# ProjV1.net
KiCad netlist of a schematic drawn in EAGLE
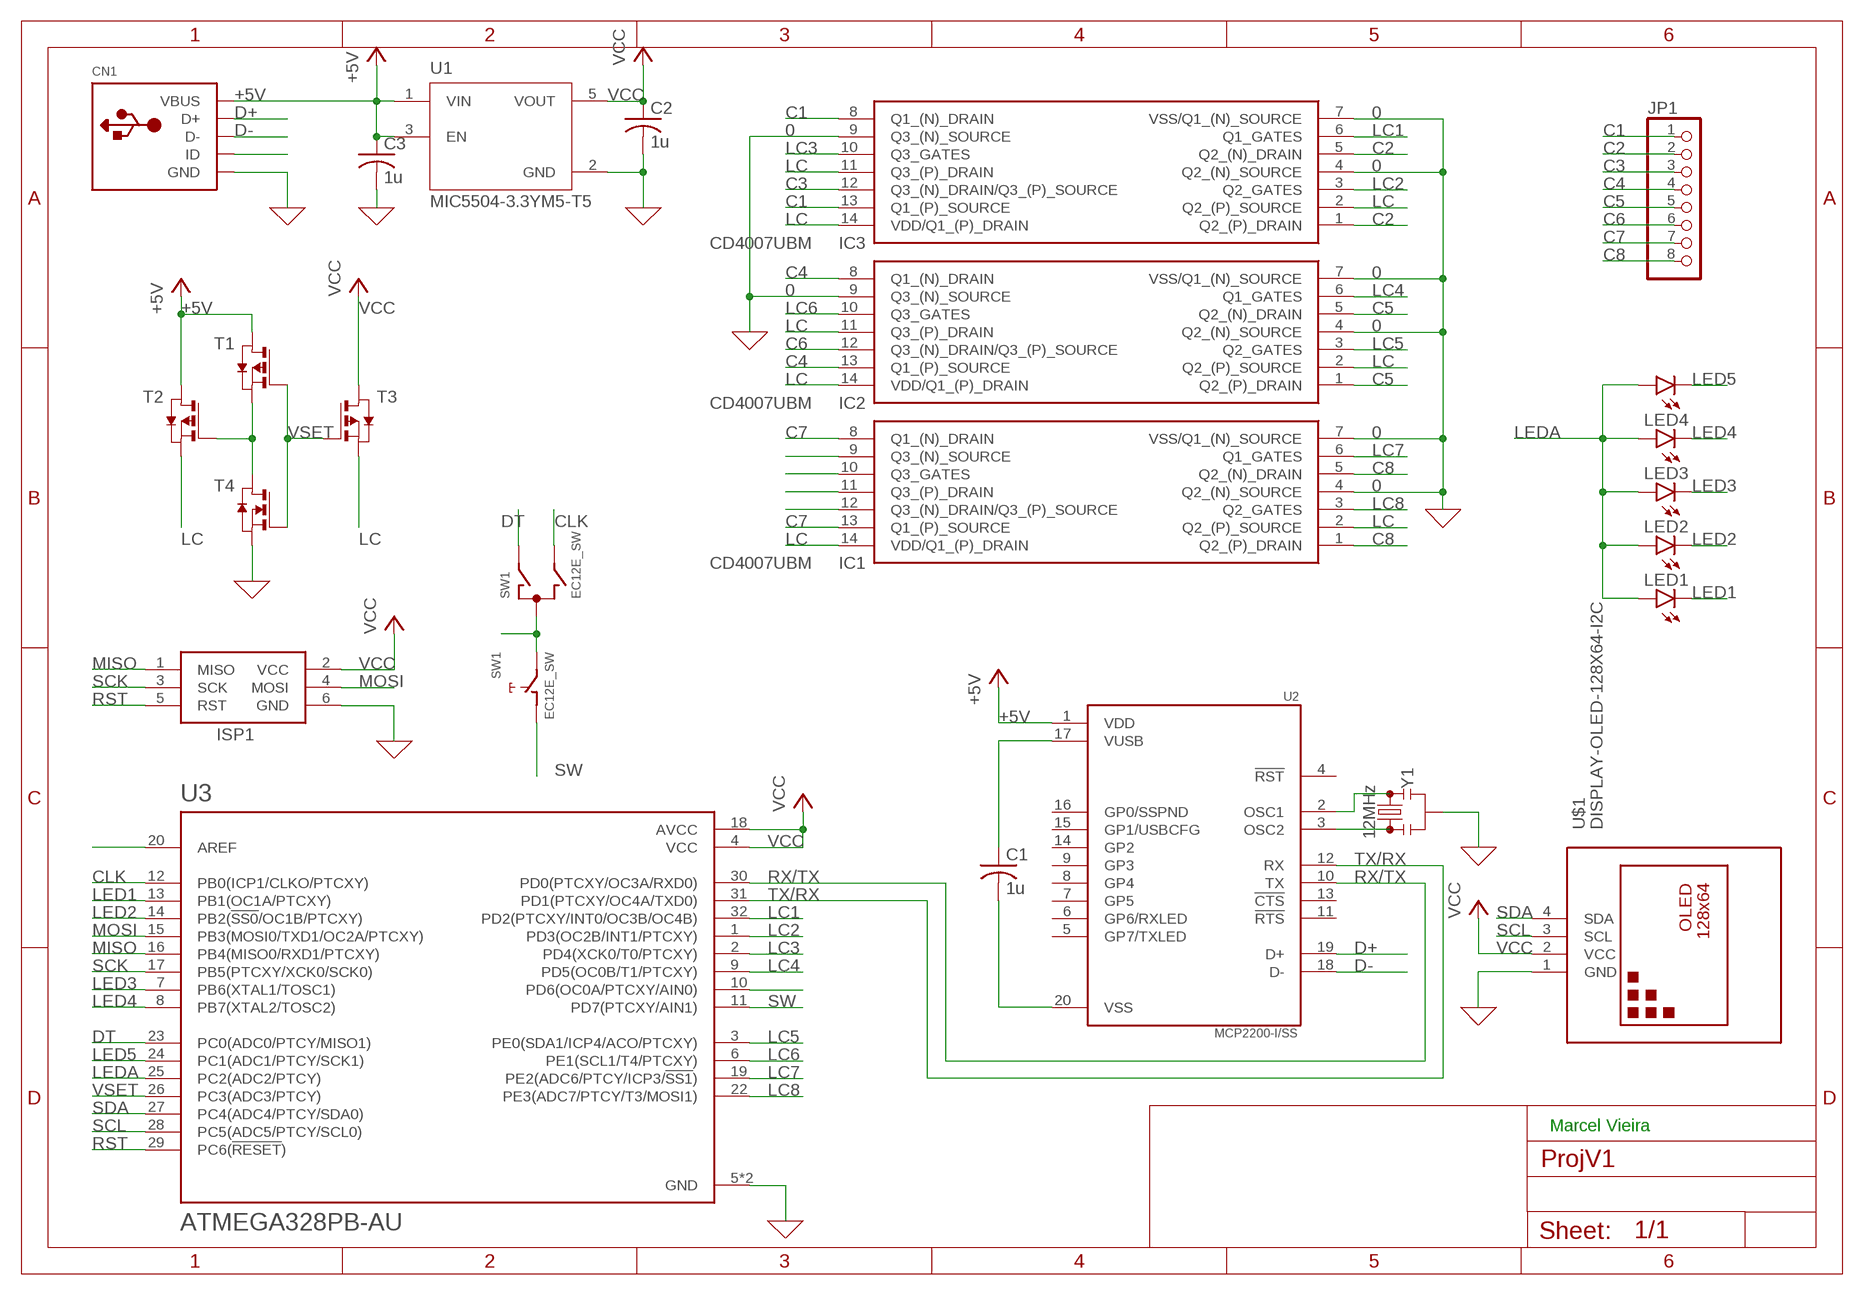
[diagram p0: schematic, sheet 1]

(export (version "E")
  (design (tool "Eeschema 10.0.6"))
  (components
    (comp (ref "C1")
      (value "1u")
      (footprint "eagle-import:C0805")
      (libsource (lib "eagle-import") (part "C-USC0805"))
    )
    (comp (ref "C2")
      (value "1u")
      (footprint "eagle-import:C0805")
      (libsource (lib "eagle-import") (part "C-USC0805"))
    )
    (comp (ref "C3")
      (value "1u")
      (footprint "eagle-import:C0805")
      (libsource (lib "eagle-import") (part "C-USC0805"))
    )
    (comp (ref "CN1")
      (value "USBMINIB")
      (footprint "eagle-import:USB-MINIB")
      (libsource (lib "eagle-import") (part "USBMINIB"))
    )
    (comp (ref "IC1")
      (value "CD4007UBM")
      (footprint "eagle-import:SOIC127P600X175-14N")
      (fields (field (name "MOUSER_PART_NUMBER") "595-CD4007UBM"))
      (libsource (lib "eagle-import") (part "CD4007UBM"))
    )
    (comp (ref "IC2")
      (value "CD4007UBM")
      (footprint "eagle-import:SOIC127P600X175-14N")
      (fields (field (name "MOUSER_PART_NUMBER") "595-CD4007UBM"))
      (libsource (lib "eagle-import") (part "CD4007UBM"))
    )
    (comp (ref "IC3")
      (value "CD4007UBM")
      (footprint "eagle-import:SOIC127P600X175-14N")
      (fields (field (name "MOUSER_PART_NUMBER") "595-CD4007UBM"))
      (libsource (lib "eagle-import") (part "CD4007UBM"))
    )
    (comp (ref "ISP1")
      (value "AVRISP-6")
      (footprint "eagle-import:AVRISP")
      (libsource (lib "eagle-import") (part "AVRISP-6"))
    )
    (comp (ref "JP1")
      (value "PINHD-1X8-3.5MM")
      (footprint "eagle-import:1X08-3.5MM")
      (libsource (lib "eagle-import") (part "PINHD-1X8-3.5MM"))
    )
    (comp (ref "LED1")
      (value "LEDCHIP-LED0805")
      (footprint "eagle-import:CHIP-LED0805")
      (libsource (lib "eagle-import") (part "LEDCHIP-LED0805"))
    )
    (comp (ref "LED2")
      (value "LEDCHIP-LED0805")
      (footprint "eagle-import:CHIP-LED0805")
      (libsource (lib "eagle-import") (part "LEDCHIP-LED0805"))
    )
    (comp (ref "LED3")
      (value "LEDCHIP-LED0805")
      (footprint "eagle-import:CHIP-LED0805")
      (libsource (lib "eagle-import") (part "LEDCHIP-LED0805"))
    )
    (comp (ref "LED4")
      (value "LEDCHIP-LED0805")
      (footprint "eagle-import:CHIP-LED0805")
      (libsource (lib "eagle-import") (part "LEDCHIP-LED0805"))
    )
    (comp (ref "LED5")
      (value "LEDCHIP-LED0805")
      (footprint "eagle-import:CHIP-LED0805")
      (libsource (lib "eagle-import") (part "LEDCHIP-LED0805"))
    )
    (comp (ref "SW1")
      (value "EC12E_SW")
      (footprint "eagle-import:ALPS_EC12E_SW")
      (fields (field (name "MPN") "EC12E2424407"))
      (libsource (lib "eagle-import") (part "EC12E_SW"))
    )
    (comp (ref "T1")
      (value "PMOSSOT23")
      (footprint "eagle-import:SOT-23")
      (libsource (lib "eagle-import") (part "PMOSSOT23"))
    )
    (comp (ref "T2")
      (value "PMOSSOT23")
      (footprint "eagle-import:SOT-23")
      (libsource (lib "eagle-import") (part "PMOSSOT23"))
    )
    (comp (ref "T3")
      (value "PMOSSOT23")
      (footprint "eagle-import:SOT-23")
      (libsource (lib "eagle-import") (part "PMOSSOT23"))
    )
    (comp (ref "T4")
      (value "NMOSSOT23")
      (footprint "eagle-import:SOT-23")
      (libsource (lib "eagle-import") (part "NMOSSOT23"))
    )
    (comp (ref "U$1")
      (value "DISPLAY-OLED-128X64-I2C")
      (footprint "eagle-import:DISPLAY-OLED-128X64-I2C")
      (libsource (lib "eagle-import") (part "DISPLAY-OLED-128X64-I2C"))
    )
    (comp (ref "U1")
      (value "MIC5504-3.3YM5-T5")
      (footprint "eagle-import:SOT95P280X145-5N")
      (fields (field (name "MF") "Microchip"))
      (libsource (lib "eagle-import") (part "MIC5504-3.3YM5-T5"))
    )
    (comp (ref "U2")
      (value "MCP2200-I/SS")
      (footprint "eagle-import:SOP65P780X200-20N")
      (fields (field (name "MF") "Microchip"))
      (libsource (lib "eagle-import") (part "MCP2200-I/SS"))
    )
    (comp (ref "U3")
      (value "ATMEGA328PB-AU")
      (footprint "eagle-import:QFP80P900X900X120-32N")
      (fields (field (name "MF") "Microchip Technology / Atmel"))
      (libsource (lib "eagle-import") (part "ATMEGA328PB-AU"))
    )
    (comp (ref "Y1")
      (value "12MHz")
      (footprint "eagle-import:RESONATOR-SMD-3.2X1.3")
      (libsource (lib "eagle-import") (part "RESONATOR-16MHZSMD_3.2X1.3"))
    )
  )
  (nets
    (net (code "1") (name "+5V") (class "Default")
      (node (ref "C3") (pin "1") (pinfunction "1_1") (pintype "passive"))
      (node (ref "CN1") (pin "VBUS") (pinfunction "VBUS_VBUS") (pintype "power_in"))
      (node (ref "T1") (pin "1") (pinfunction "D_1") (pintype "passive"))
      (node (ref "T2") (pin "1") (pinfunction "D_1") (pintype "passive"))
      (node (ref "U1") (pin "1") (pinfunction "VIN_1") (pintype "input"))
      (node (ref "U1") (pin "3") (pinfunction "EN_3") (pintype "input"))
      (node (ref "U2") (pin "1") (pinfunction "VDD_1") (pintype "power_in"))
    )
    (net (code "2") (name "/C1") (class "Default")
      (node (ref "IC3") (pin "13") (pinfunction "Q1_(P)_SOURCE_13") (pintype "bidirectional"))
      (node (ref "IC3") (pin "8") (pinfunction "Q1_(N)_DRAIN_8") (pintype "bidirectional"))
      (node (ref "JP1") (pin "1") (pinfunction "1_1") (pintype "passive"))
    )
    (net (code "3") (name "/C2") (class "Default")
      (node (ref "IC3") (pin "1") (pinfunction "Q2_(P)_DRAIN_1") (pintype "bidirectional"))
      (node (ref "IC3") (pin "5") (pinfunction "Q2_(N)_DRAIN_5") (pintype "bidirectional"))
      (node (ref "JP1") (pin "2") (pinfunction "2_2") (pintype "passive"))
    )
    (net (code "4") (name "/C3") (class "Default")
      (node (ref "IC3") (pin "12") (pinfunction "Q3_(N)_DRAIN/Q3_(P)_SOURCE_12") (pintype "bidirectional"))
      (node (ref "JP1") (pin "3") (pinfunction "3_3") (pintype "passive"))
    )
    (net (code "5") (name "/C4") (class "Default")
      (node (ref "IC2") (pin "13") (pinfunction "Q1_(P)_SOURCE_13") (pintype "bidirectional"))
      (node (ref "IC2") (pin "8") (pinfunction "Q1_(N)_DRAIN_8") (pintype "bidirectional"))
      (node (ref "JP1") (pin "4") (pinfunction "4_4") (pintype "passive"))
    )
    (net (code "6") (name "/C5") (class "Default")
      (node (ref "IC2") (pin "1") (pinfunction "Q2_(P)_DRAIN_1") (pintype "bidirectional"))
      (node (ref "IC2") (pin "5") (pinfunction "Q2_(N)_DRAIN_5") (pintype "bidirectional"))
      (node (ref "JP1") (pin "5") (pinfunction "5_5") (pintype "passive"))
    )
    (net (code "7") (name "/C6") (class "Default")
      (node (ref "IC2") (pin "12") (pinfunction "Q3_(N)_DRAIN/Q3_(P)_SOURCE_12") (pintype "bidirectional"))
      (node (ref "JP1") (pin "6") (pinfunction "6_6") (pintype "passive"))
    )
    (net (code "8") (name "/C7") (class "Default")
      (node (ref "IC1") (pin "13") (pinfunction "Q1_(P)_SOURCE_13") (pintype "bidirectional"))
      (node (ref "IC1") (pin "8") (pinfunction "Q1_(N)_DRAIN_8") (pintype "bidirectional"))
      (node (ref "JP1") (pin "7") (pinfunction "7_7") (pintype "passive"))
    )
    (net (code "9") (name "/C8") (class "Default")
      (node (ref "IC1") (pin "1") (pinfunction "Q2_(P)_DRAIN_1") (pintype "bidirectional"))
      (node (ref "IC1") (pin "5") (pinfunction "Q2_(N)_DRAIN_5") (pintype "bidirectional"))
      (node (ref "JP1") (pin "8") (pinfunction "8_8") (pintype "passive"))
    )
    (net (code "10") (name "/CLK") (class "Default")
      (node (ref "SW1") (pin "B") (pinfunction "B_B") (pintype "passive"))
      (node (ref "U3") (pin "12") (pinfunction "PB0(ICP1/CLKO/PTCXY)_12") (pintype "bidirectional"))
    )
    (net (code "11") (name "/D+") (class "Default")
      (node (ref "CN1") (pin "D+") (pinfunction "D+_D+") (pintype "bidirectional"))
      (node (ref "U2") (pin "19") (pinfunction "D+_19") (pintype "bidirectional"))
    )
    (net (code "12") (name "/D-") (class "Default")
      (node (ref "CN1") (pin "D-") (pinfunction "D-_D-") (pintype "bidirectional"))
      (node (ref "U2") (pin "18") (pinfunction "D-_18") (pintype "bidirectional"))
    )
    (net (code "13") (name "/DT") (class "Default")
      (node (ref "SW1") (pin "A") (pinfunction "A_A") (pintype "passive"))
      (node (ref "U3") (pin "23") (pinfunction "PC0(ADC0/PTCY/MISO1)_23") (pintype "bidirectional"))
    )
    (net (code "14") (name "/LC") (class "Default")
      (node (ref "IC1") (pin "14") (pinfunction "VDD/Q1_(P)_DRAIN_14") (pintype "bidirectional"))
      (node (ref "IC1") (pin "2") (pinfunction "Q2_(P)_SOURCE_2") (pintype "bidirectional"))
      (node (ref "IC2") (pin "11") (pinfunction "Q3_(P)_DRAIN_11") (pintype "bidirectional"))
      (node (ref "IC2") (pin "14") (pinfunction "VDD/Q1_(P)_DRAIN_14") (pintype "bidirectional"))
      (node (ref "IC2") (pin "2") (pinfunction "Q2_(P)_SOURCE_2") (pintype "bidirectional"))
      (node (ref "IC3") (pin "11") (pinfunction "Q3_(P)_DRAIN_11") (pintype "bidirectional"))
      (node (ref "IC3") (pin "14") (pinfunction "VDD/Q1_(P)_DRAIN_14") (pintype "bidirectional"))
      (node (ref "IC3") (pin "2") (pinfunction "Q2_(P)_SOURCE_2") (pintype "bidirectional"))
      (node (ref "T2") (pin "2") (pinfunction "S_2") (pintype "passive"))
      (node (ref "T3") (pin "2") (pinfunction "S_2") (pintype "passive"))
    )
    (net (code "15") (name "/LC1") (class "Default")
      (node (ref "IC3") (pin "6") (pinfunction "Q1_GATES_6") (pintype "bidirectional"))
      (node (ref "U3") (pin "32") (pinfunction "PD2(PTCXY/INT0/OC3B/OC4B)_32") (pintype "bidirectional"))
    )
    (net (code "16") (name "/LC2") (class "Default")
      (node (ref "IC3") (pin "3") (pinfunction "Q2_GATES_3") (pintype "bidirectional"))
      (node (ref "U3") (pin "1") (pinfunction "PD3(OC2B/INT1/PTCXY)_1") (pintype "bidirectional"))
    )
    (net (code "17") (name "/LC3") (class "Default")
      (node (ref "IC3") (pin "10") (pinfunction "Q3_GATES_10") (pintype "bidirectional"))
      (node (ref "U3") (pin "2") (pinfunction "PD4(XCK0/T0/PTCXY)_2") (pintype "bidirectional"))
    )
    (net (code "18") (name "/LC4") (class "Default")
      (node (ref "IC2") (pin "6") (pinfunction "Q1_GATES_6") (pintype "bidirectional"))
      (node (ref "U3") (pin "9") (pinfunction "PD5(OC0B/T1/PTCXY)_9") (pintype "bidirectional"))
    )
    (net (code "19") (name "/LC5") (class "Default")
      (node (ref "IC2") (pin "3") (pinfunction "Q2_GATES_3") (pintype "bidirectional"))
      (node (ref "U3") (pin "3") (pinfunction "PE0(SDA1/ICP4/ACO/PTCXY)_3") (pintype "bidirectional"))
    )
    (net (code "20") (name "/LC6") (class "Default")
      (node (ref "IC2") (pin "10") (pinfunction "Q3_GATES_10") (pintype "bidirectional"))
      (node (ref "U3") (pin "6") (pinfunction "PE1(SCL1/T4/PTCXY)_6") (pintype "bidirectional"))
    )
    (net (code "21") (name "/LC7") (class "Default")
      (node (ref "IC1") (pin "6") (pinfunction "Q1_GATES_6") (pintype "bidirectional"))
      (node (ref "U3") (pin "19") (pinfunction "PE2(ADC6/PTCY/ICP3/~{SS1})_19") (pintype "bidirectional"))
    )
    (net (code "22") (name "/LC8") (class "Default")
      (node (ref "IC1") (pin "3") (pinfunction "Q2_GATES_3") (pintype "bidirectional"))
      (node (ref "U3") (pin "22") (pinfunction "PE3(ADC7/PTCY/T3/MOSI1)_22") (pintype "bidirectional"))
    )
    (net (code "23") (name "/LED1") (class "Default")
      (node (ref "LED1") (pin "C") (pinfunction "C_C") (pintype "passive"))
      (node (ref "U3") (pin "13") (pinfunction "PB1(OC1A/PTCXY)_13") (pintype "bidirectional"))
    )
    (net (code "24") (name "/LED2") (class "Default")
      (node (ref "LED2") (pin "C") (pinfunction "C_C") (pintype "passive"))
      (node (ref "U3") (pin "14") (pinfunction "PB2(~{SS0}/OC1B/PTCXY)_14") (pintype "bidirectional"))
    )
    (net (code "25") (name "/LED3") (class "Default")
      (node (ref "LED3") (pin "C") (pinfunction "C_C") (pintype "passive"))
      (node (ref "U3") (pin "7") (pinfunction "PB6(XTAL1/TOSC1)_7") (pintype "bidirectional"))
    )
    (net (code "26") (name "/LED4") (class "Default")
      (node (ref "LED4") (pin "C") (pinfunction "C_C") (pintype "passive"))
      (node (ref "U3") (pin "8") (pinfunction "PB7(XTAL2/TOSC2)_8") (pintype "bidirectional"))
    )
    (net (code "27") (name "/LED5") (class "Default")
      (node (ref "LED5") (pin "C") (pinfunction "C_C") (pintype "passive"))
      (node (ref "U3") (pin "24") (pinfunction "PC1(ADC1/PTCY/SCK1)_24") (pintype "bidirectional"))
    )
    (net (code "28") (name "/LEDA") (class "Default")
      (node (ref "LED1") (pin "A") (pinfunction "A_A") (pintype "passive"))
      (node (ref "LED2") (pin "A") (pinfunction "A_A") (pintype "passive"))
      (node (ref "LED3") (pin "A") (pinfunction "A_A") (pintype "passive"))
      (node (ref "LED4") (pin "A") (pinfunction "A_A") (pintype "passive"))
      (node (ref "LED5") (pin "A") (pinfunction "A_A") (pintype "passive"))
      (node (ref "U3") (pin "25") (pinfunction "PC2(ADC2/PTCY)_25") (pintype "bidirectional"))
    )
    (net (code "29") (name "/MISO") (class "Default")
      (node (ref "ISP1") (pin "1") (pinfunction "MISO_1") (pintype "input"))
      (node (ref "U3") (pin "16") (pinfunction "PB4(MISO0/RXD1/PTCXY)_16") (pintype "bidirectional"))
    )
    (net (code "30") (name "/MOSI") (class "Default")
      (node (ref "ISP1") (pin "4") (pinfunction "MOSI_4") (pintype "output"))
      (node (ref "U3") (pin "15") (pinfunction "PB3(MOSI0/TXD1/OC2A/PTCXY)_15") (pintype "bidirectional"))
    )
    (net (code "31") (name "/RST") (class "Default")
      (node (ref "ISP1") (pin "5") (pinfunction "RST_5") (pintype "output"))
      (node (ref "U3") (pin "29") (pinfunction "PC6(~{RESET})_29") (pintype "bidirectional"))
    )
    (net (code "32") (name "/RX{slash}TX") (class "Default")
      (node (ref "U2") (pin "10") (pinfunction "TX_10") (pintype "output"))
      (node (ref "U3") (pin "30") (pinfunction "PD0(PTCXY/OC3A/RXD0)_30") (pintype "bidirectional"))
    )
    (net (code "33") (name "/SCK") (class "Default")
      (node (ref "ISP1") (pin "3") (pinfunction "SCK_3") (pintype "output"))
      (node (ref "U3") (pin "17") (pinfunction "PB5(PTCXY/XCK0/SCK0)_17") (pintype "bidirectional"))
    )
    (net (code "34") (name "/SCL") (class "Default")
      (node (ref "U$1") (pin "3") (pinfunction "SCL_3") (pintype "bidirectional"))
      (node (ref "U3") (pin "28") (pinfunction "PC5(ADC5/PTCY/SCL0)_28") (pintype "bidirectional"))
    )
    (net (code "35") (name "/SDA") (class "Default")
      (node (ref "U$1") (pin "4") (pinfunction "SDA_4") (pintype "bidirectional"))
      (node (ref "U3") (pin "27") (pinfunction "PC4(ADC4/PTCY/SDA0)_27") (pintype "bidirectional"))
    )
    (net (code "36") (name "/SW") (class "Default")
      (node (ref "SW1") (pin "D") (pinfunction "1_D") (pintype "passive"))
      (node (ref "U3") (pin "11") (pinfunction "PD7(PTCXY/AIN1)_11") (pintype "bidirectional"))
    )
    (net (code "37") (name "/TX{slash}RX") (class "Default")
      (node (ref "U2") (pin "12") (pinfunction "RX_12") (pintype "input"))
      (node (ref "U3") (pin "31") (pinfunction "PD1(PTCXY/OC4A/TXD0)_31") (pintype "bidirectional"))
    )
    (net (code "38") (name "/VSET") (class "Default")
      (node (ref "T1") (pin "3") (pinfunction "G_3") (pintype "passive"))
      (node (ref "T3") (pin "3") (pinfunction "G_3") (pintype "passive"))
      (node (ref "T4") (pin "3") (pinfunction "G_3") (pintype "passive"))
      (node (ref "U3") (pin "26") (pinfunction "PC3(ADC3/PTCY)_26") (pintype "bidirectional"))
    )
    (net (code "39") (name "GND") (class "Default")
      (node (ref "C2") (pin "2") (pinfunction "2_2") (pintype "passive"))
      (node (ref "C3") (pin "2") (pinfunction "2_2") (pintype "passive"))
      (node (ref "CN1") (pin "GND") (pinfunction "GND_GND") (pintype "power_in"))
      (node (ref "IC1") (pin "4") (pinfunction "Q2_(N)_SOURCE_4") (pintype "bidirectional"))
      (node (ref "IC1") (pin "7") (pinfunction "VSS/Q1_(N)_SOURCE_7") (pintype "bidirectional"))
      (node (ref "IC2") (pin "4") (pinfunction "Q2_(N)_SOURCE_4") (pintype "bidirectional"))
      (node (ref "IC2") (pin "7") (pinfunction "VSS/Q1_(N)_SOURCE_7") (pintype "bidirectional"))
      (node (ref "IC2") (pin "9") (pinfunction "Q3_(N)_SOURCE_9") (pintype "bidirectional"))
      (node (ref "IC3") (pin "4") (pinfunction "Q2_(N)_SOURCE_4") (pintype "bidirectional"))
      (node (ref "IC3") (pin "7") (pinfunction "VSS/Q1_(N)_SOURCE_7") (pintype "bidirectional"))
      (node (ref "IC3") (pin "9") (pinfunction "Q3_(N)_SOURCE_9") (pintype "bidirectional"))
      (node (ref "ISP1") (pin "6") (pinfunction "GND_6") (pintype "power_in"))
      (node (ref "T4") (pin "2") (pinfunction "S_2") (pintype "passive"))
      (node (ref "U$1") (pin "1") (pinfunction "GND_1") (pintype "power_in"))
      (node (ref "U1") (pin "2") (pinfunction "GND_2") (pintype "power_in"))
      (node (ref "U3") (pin "21") (pinfunction "GND_21") (pintype "power_in"))
      (node (ref "U3") (pin "5") (pinfunction "GND_5") (pintype "power_in"))
      (node (ref "Y1") (pin "2") (pinfunction "2_2") (pintype "passive"))
    )
    (net (code "40") (name "Net-(SW1B-2)") (class "Default")
      (node (ref "SW1") (pin "C") (pinfunction "C_C") (pintype "passive"))
      (node (ref "SW1") (pin "E") (pinfunction "2_E") (pintype "passive"))
    )
    (net (code "41") (name "Net-(T1-S)") (class "Default")
      (node (ref "T1") (pin "2") (pinfunction "S_2") (pintype "passive"))
      (node (ref "T2") (pin "3") (pinfunction "G_3") (pintype "passive"))
      (node (ref "T4") (pin "1") (pinfunction "D_1") (pintype "passive"))
    )
    (net (code "42") (name "Net-(U2-OSC1)") (class "Default")
      (node (ref "U2") (pin "2") (pinfunction "OSC1_2") (pintype "input"))
      (node (ref "Y1") (pin "1") (pinfunction "1_1") (pintype "passive"))
    )
    (net (code "43") (name "Net-(U2-OSC2)") (class "Default")
      (node (ref "U2") (pin "3") (pinfunction "OSC2_3") (pintype "output"))
      (node (ref "Y1") (pin "3") (pinfunction "3_3") (pintype "passive"))
    )
    (net (code "44") (name "Net-(U2-VSS)") (class "Default")
      (node (ref "C1") (pin "2") (pinfunction "2_2") (pintype "passive"))
      (node (ref "U2") (pin "20") (pinfunction "VSS_20") (pintype "power_in"))
    )
    (net (code "45") (name "Net-(U2-VUSB)") (class "Default")
      (node (ref "C1") (pin "1") (pinfunction "1_1") (pintype "passive"))
      (node (ref "U2") (pin "17") (pinfunction "VUSB_17") (pintype "power_in"))
    )
    (net (code "46") (name "VCC") (class "Default")
      (node (ref "C2") (pin "1") (pinfunction "1_1") (pintype "passive"))
      (node (ref "ISP1") (pin "2") (pinfunction "VCC_2") (pintype "power_in"))
      (node (ref "T3") (pin "1") (pinfunction "D_1") (pintype "passive"))
      (node (ref "U$1") (pin "2") (pinfunction "VCC_2") (pintype "power_in"))
      (node (ref "U1") (pin "5") (pinfunction "VOUT_5") (pintype "output"))
      (node (ref "U3") (pin "18") (pinfunction "AVCC_18") (pintype "power_in"))
      (node (ref "U3") (pin "4") (pinfunction "VCC_4") (pintype "power_in"))
    )
    (net (code "47") (name "unconnected-(CN1-PadID)") (class "Default")
      (node (ref "CN1") (pin "ID") (pinfunction "ID_ID") (pintype "bidirectional"))
    )
    (net (code "48") (name "unconnected-(IC1-Q3_(N)_DRAIN{slash}Q3_(P)_SOURCE-Pad12)") (class "Default")
      (node (ref "IC1") (pin "12") (pinfunction "Q3_(N)_DRAIN/Q3_(P)_SOURCE_12") (pintype "bidirectional"))
    )
    (net (code "49") (name "unconnected-(IC1-Q3_(N)_SOURCE-Pad9)") (class "Default")
      (node (ref "IC1") (pin "9") (pinfunction "Q3_(N)_SOURCE_9") (pintype "bidirectional"))
    )
    (net (code "50") (name "unconnected-(IC1-Q3_(P)_DRAIN-Pad11)") (class "Default")
      (node (ref "IC1") (pin "11") (pinfunction "Q3_(P)_DRAIN_11") (pintype "bidirectional"))
    )
    (net (code "51") (name "unconnected-(IC1-Q3_GATES-Pad10)") (class "Default")
      (node (ref "IC1") (pin "10") (pinfunction "Q3_GATES_10") (pintype "bidirectional"))
    )
    (net (code "52") (name "unconnected-(U2-GP0{slash}SSPND-Pad16)") (class "Default")
      (node (ref "U2") (pin "16") (pinfunction "GP0/SSPND_16") (pintype "bidirectional"))
    )
    (net (code "53") (name "unconnected-(U2-GP1{slash}USBCFG-Pad15)") (class "Default")
      (node (ref "U2") (pin "15") (pinfunction "GP1/USBCFG_15") (pintype "bidirectional"))
    )
    (net (code "54") (name "unconnected-(U2-GP2-Pad14)") (class "Default")
      (node (ref "U2") (pin "14") (pinfunction "GP2_14") (pintype "bidirectional"))
    )
    (net (code "55") (name "unconnected-(U2-GP3-Pad9)") (class "Default")
      (node (ref "U2") (pin "9") (pinfunction "GP3_9") (pintype "bidirectional"))
    )
    (net (code "56") (name "unconnected-(U2-GP4-Pad8)") (class "Default")
      (node (ref "U2") (pin "8") (pinfunction "GP4_8") (pintype "bidirectional"))
    )
    (net (code "57") (name "unconnected-(U2-GP5-Pad7)") (class "Default")
      (node (ref "U2") (pin "7") (pinfunction "GP5_7") (pintype "bidirectional"))
    )
    (net (code "58") (name "unconnected-(U2-GP6{slash}RXLED-Pad6)") (class "Default")
      (node (ref "U2") (pin "6") (pinfunction "GP6/RXLED_6") (pintype "bidirectional"))
    )
    (net (code "59") (name "unconnected-(U2-GP7{slash}TXLED-Pad5)") (class "Default")
      (node (ref "U2") (pin "5") (pinfunction "GP7/TXLED_5") (pintype "bidirectional"))
    )
    (net (code "60") (name "unconnected-(U2-~{CTS}-Pad13)") (class "Default")
      (node (ref "U2") (pin "13") (pinfunction "~{CTS}_13") (pintype "input"))
    )
    (net (code "61") (name "unconnected-(U2-~{RST}-Pad4)") (class "Default")
      (node (ref "U2") (pin "4") (pinfunction "~{RST}_4") (pintype "input"))
    )
    (net (code "62") (name "unconnected-(U2-~{RTS}-Pad11)") (class "Default")
      (node (ref "U2") (pin "11") (pinfunction "~{RTS}_11") (pintype "output"))
    )
    (net (code "63") (name "unconnected-(U3-AREF-Pad20)") (class "Default")
      (node (ref "U3") (pin "20") (pinfunction "AREF_20") (pintype "input"))
    )
    (net (code "64") (name "unconnected-(U3-PD6(OC0A{slash}PTCXY{slash}AIN0)-Pad10)") (class "Default")
      (node (ref "U3") (pin "10") (pinfunction "PD6(OC0A/PTCXY/AIN0)_10") (pintype "bidirectional"))
    )
  )
)
